# nu-multi-6-mounting_board.net
KiCad netlist of a schematic drawn in EAGLE
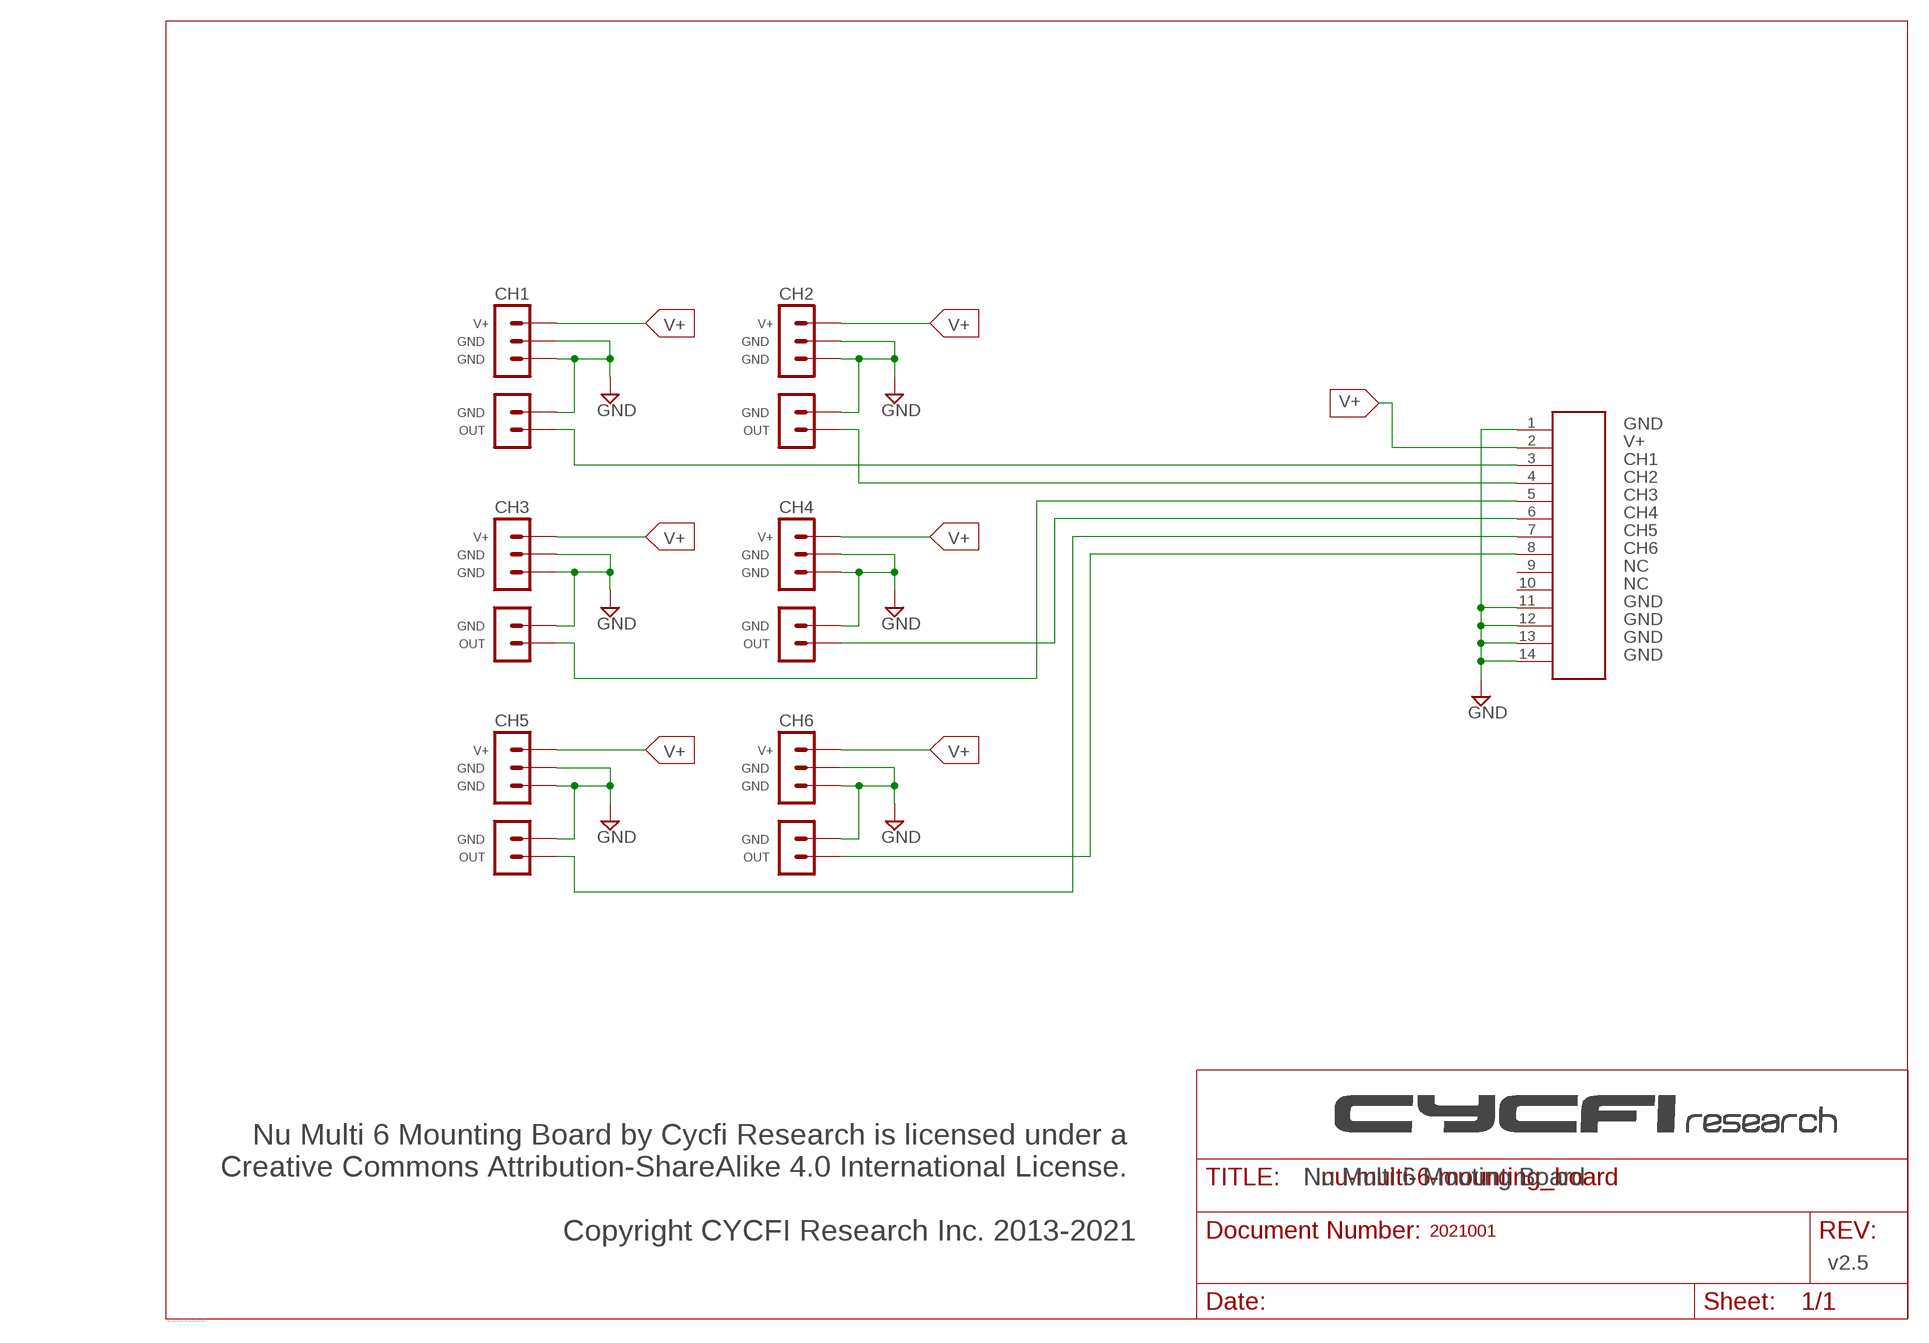
[diagram p0: schematic, sheet 1]

(export (version "E")
  (design (tool "Eeschema 10.0.6"))
  (components
    (comp (ref "CH1")
      (value "NU-CAPSULE")
      (footprint "eagle-import:NU-CAPSULE")
      (libsource (lib "eagle-import") (part "NU-CAPSULE"))
    )
    (comp (ref "CH2")
      (value "NU-CAPSULE")
      (footprint "eagle-import:NU-CAPSULE")
      (libsource (lib "eagle-import") (part "NU-CAPSULE"))
    )
    (comp (ref "CH3")
      (value "NU-CAPSULE")
      (footprint "eagle-import:NU-CAPSULE")
      (libsource (lib "eagle-import") (part "NU-CAPSULE"))
    )
    (comp (ref "CH4")
      (value "NU-CAPSULE")
      (footprint "eagle-import:NU-CAPSULE")
      (libsource (lib "eagle-import") (part "NU-CAPSULE"))
    )
    (comp (ref "CH5")
      (value "NU-CAPSULE")
      (footprint "eagle-import:NU-CAPSULE")
      (libsource (lib "eagle-import") (part "NU-CAPSULE"))
    )
    (comp (ref "CH6")
      (value "NU-CAPSULE")
      (footprint "eagle-import:NU-CAPSULE")
      (libsource (lib "eagle-import") (part "NU-CAPSULE"))
    )
    (comp (ref "U$1")
      (value "2X7-1MM-HEADER")
      (footprint "eagle-import:2X7-1MM")
      (libsource (lib "eagle-import") (part "2X7-1MM-HEADER"))
    )
  )
  (nets
    (net (code "1") (name "/V+") (class "Default")
      (node (ref "CH1") (pin "P$1") (pinfunction "P1_P$1") (pintype "passive"))
      (node (ref "CH2") (pin "P$1") (pinfunction "P1_P$1") (pintype "passive"))
      (node (ref "CH3") (pin "P$1") (pinfunction "P1_P$1") (pintype "passive"))
      (node (ref "CH4") (pin "P$1") (pinfunction "P1_P$1") (pintype "passive"))
      (node (ref "CH5") (pin "P$1") (pinfunction "P1_P$1") (pintype "passive"))
      (node (ref "CH6") (pin "P$1") (pinfunction "P1_P$1") (pintype "passive"))
      (node (ref "U$1") (pin "2") (pinfunction "P$2_2") (pintype "bidirectional"))
    )
    (net (code "2") (name "GND") (class "Default")
      (node (ref "CH1") (pin "P$2") (pinfunction "P2_P$2") (pintype "passive"))
      (node (ref "CH1") (pin "P$3") (pinfunction "P3_P$3") (pintype "passive"))
      (node (ref "CH1") (pin "P$4") (pinfunction "P4_P$4") (pintype "passive"))
      (node (ref "CH2") (pin "P$2") (pinfunction "P2_P$2") (pintype "passive"))
      (node (ref "CH2") (pin "P$3") (pinfunction "P3_P$3") (pintype "passive"))
      (node (ref "CH2") (pin "P$4") (pinfunction "P4_P$4") (pintype "passive"))
      (node (ref "CH3") (pin "P$2") (pinfunction "P2_P$2") (pintype "passive"))
      (node (ref "CH3") (pin "P$3") (pinfunction "P3_P$3") (pintype "passive"))
      (node (ref "CH3") (pin "P$4") (pinfunction "P4_P$4") (pintype "passive"))
      (node (ref "CH4") (pin "P$2") (pinfunction "P2_P$2") (pintype "passive"))
      (node (ref "CH4") (pin "P$3") (pinfunction "P3_P$3") (pintype "passive"))
      (node (ref "CH4") (pin "P$4") (pinfunction "P4_P$4") (pintype "passive"))
      (node (ref "CH5") (pin "P$2") (pinfunction "P2_P$2") (pintype "passive"))
      (node (ref "CH5") (pin "P$3") (pinfunction "P3_P$3") (pintype "passive"))
      (node (ref "CH5") (pin "P$4") (pinfunction "P4_P$4") (pintype "passive"))
      (node (ref "CH6") (pin "P$2") (pinfunction "P2_P$2") (pintype "passive"))
      (node (ref "CH6") (pin "P$3") (pinfunction "P3_P$3") (pintype "passive"))
      (node (ref "CH6") (pin "P$4") (pinfunction "P4_P$4") (pintype "passive"))
      (node (ref "U$1") (pin "1") (pinfunction "P$1_1") (pintype "bidirectional"))
      (node (ref "U$1") (pin "11") (pinfunction "P$11_11") (pintype "bidirectional"))
      (node (ref "U$1") (pin "12") (pinfunction "P$12_12") (pintype "bidirectional"))
      (node (ref "U$1") (pin "13") (pinfunction "P$13_13") (pintype "bidirectional"))
      (node (ref "U$1") (pin "14") (pinfunction "P$14_14") (pintype "bidirectional"))
    )
    (net (code "3") (name "Net-(CH1-P5)") (class "Default")
      (node (ref "CH1") (pin "P$5") (pinfunction "P5_P$5") (pintype "passive"))
      (node (ref "U$1") (pin "3") (pinfunction "P$3_3") (pintype "bidirectional"))
    )
    (net (code "4") (name "Net-(CH2-P5)") (class "Default")
      (node (ref "CH2") (pin "P$5") (pinfunction "P5_P$5") (pintype "passive"))
      (node (ref "U$1") (pin "4") (pinfunction "P$4_4") (pintype "bidirectional"))
    )
    (net (code "5") (name "Net-(CH3-P5)") (class "Default")
      (node (ref "CH3") (pin "P$5") (pinfunction "P5_P$5") (pintype "passive"))
      (node (ref "U$1") (pin "5") (pinfunction "P$5_5") (pintype "bidirectional"))
    )
    (net (code "6") (name "Net-(CH4-P5)") (class "Default")
      (node (ref "CH4") (pin "P$5") (pinfunction "P5_P$5") (pintype "passive"))
      (node (ref "U$1") (pin "6") (pinfunction "P$6_6") (pintype "bidirectional"))
    )
    (net (code "7") (name "Net-(CH5-P5)") (class "Default")
      (node (ref "CH5") (pin "P$5") (pinfunction "P5_P$5") (pintype "passive"))
      (node (ref "U$1") (pin "7") (pinfunction "P$7_7") (pintype "bidirectional"))
    )
    (net (code "8") (name "Net-(CH6-P5)") (class "Default")
      (node (ref "CH6") (pin "P$5") (pinfunction "P5_P$5") (pintype "passive"))
      (node (ref "U$1") (pin "8") (pinfunction "P$8_8") (pintype "bidirectional"))
    )
    (net (code "9") (name "unconnected-(U$1-P$9-Pad9)") (class "Default")
      (node (ref "U$1") (pin "9") (pinfunction "P$9_9") (pintype "bidirectional"))
    )
    (net (code "10") (name "unconnected-(U$1-P$10-Pad10)") (class "Default")
      (node (ref "U$1") (pin "10") (pinfunction "P$10_10") (pintype "bidirectional"))
    )
  )
)
